# Buzzer.net
KiCad netlist of a schematic drawn in Altium Designer
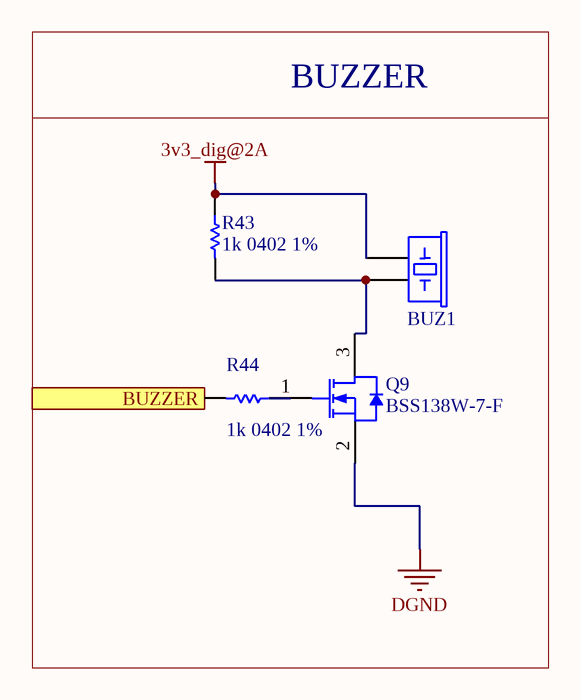
[diagram p0: Buzzer.SchDoc]

(export (version "E")
  (design (tool "Eeschema 10.0.6"))
  (components
    (comp (ref "BUZ1")
      (value "CUI CMT-1285C-035")
      (footprint "BUZZER-12MM-NS")
      (description "Audio Buzzer Magnetic 3Vo-p 5Vo-p 70mA 3.5Vo-p 85dB Through Hole Pin Tray")
      (fields (field (name "MANUFACTURER PART NUMBER") "CMT-1285C-035"))
      (libsource (lib "in3ator") (part "CMP-581a9557be5887dd-1"))
    )
    (comp (ref "Q9")
      (value "BSS138W-7-F")
      (footprint "DIOD-SOT323-3_V")
      (fields (field (name "MANUFACTURER") "DiodesIncorporated"))
      (libsource (lib "Altium Content Vault") (part "NEMOS-GSD-3"))
    )
    (comp (ref "R43")
      (value "1k 0402 1%")
      (footprint "RESC1005X40X25ML05T10")
      (libsource (lib "Altium Content Vault") (part "RES"))
    )
    (comp (ref "R44")
      (value "1k 0402 1%")
      (footprint "RESC1005X40X25ML05T10")
      (libsource (lib "Altium Content Vault") (part "RES"))
    )
  )
  (nets
    (net (code "1") (name "/BUZZER") (class "Default")
      (node (ref "R44") (pin "2") (pinfunction "2_2") (pintype "passive"))
    )
    (net (code "2") (name "3v3_dig@2A") (class "Default")
      (node (ref "BUZ1") (pin "1") (pinfunction "+_1") (pintype "passive"))
      (node (ref "R43") (pin "1") (pinfunction "1_1") (pintype "passive"))
    )
    (net (code "3") (name "DGND") (class "Default")
      (node (ref "Q9") (pin "2") (pinfunction "S_2") (pintype "passive"))
    )
    (net (code "4") (name "Net-(BUZ1--)") (class "Default")
      (node (ref "BUZ1") (pin "2") (pinfunction "-_2") (pintype "passive"))
      (node (ref "Q9") (pin "3") (pinfunction "D_3") (pintype "passive"))
      (node (ref "R43") (pin "2") (pinfunction "2_2") (pintype "passive"))
    )
    (net (code "5") (name "Net-(Q9-G)") (class "Default")
      (node (ref "Q9") (pin "1") (pinfunction "G_1") (pintype "passive"))
      (node (ref "R44") (pin "1") (pinfunction "1_1") (pintype "passive"))
    )
  )
)
